# v1.net
KiCad netlist of a schematic drawn in EAGLE
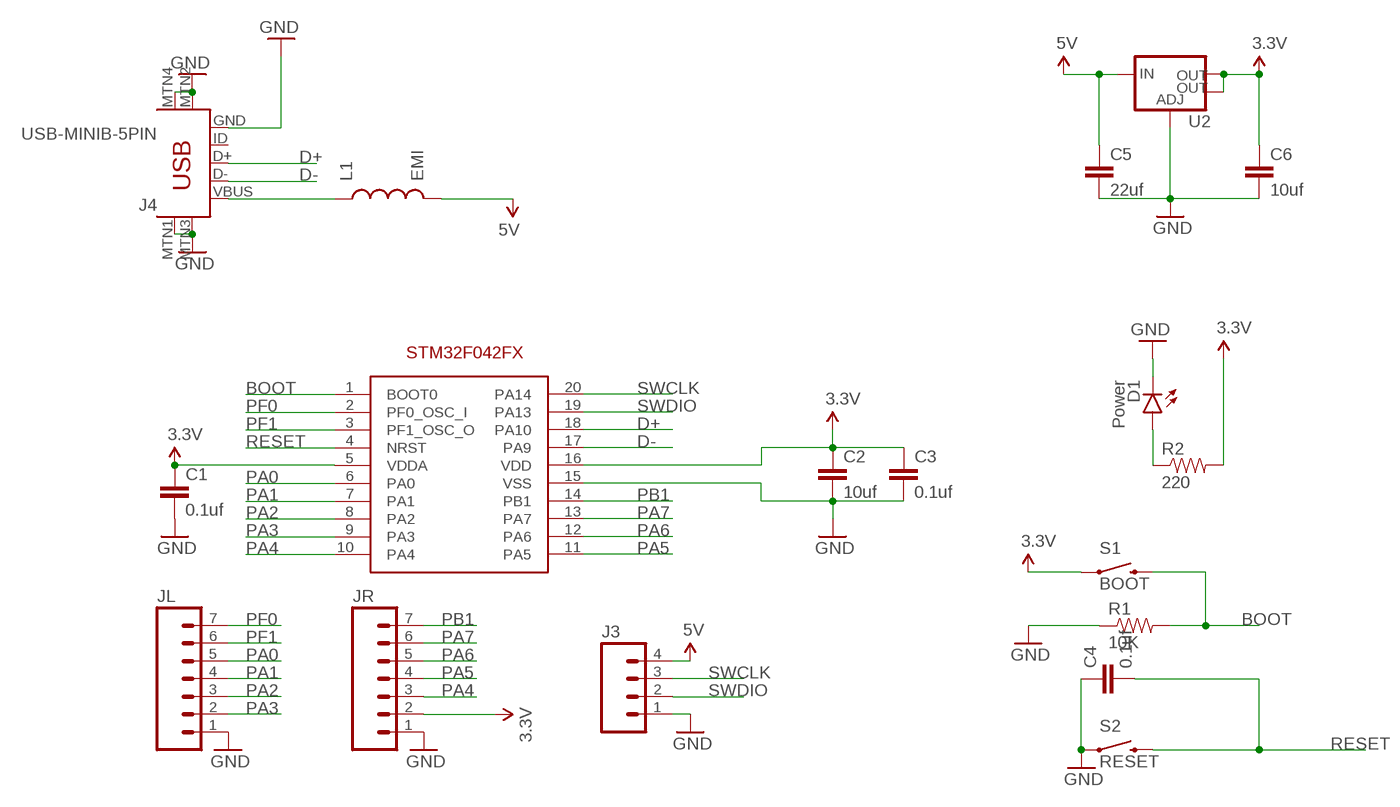
[diagram p0: schematic, sheet 1]

(export (version "E")
  (design (tool "Eeschema 10.0.6"))
  (components
    (comp (ref "C1")
      (value "0.1uf")
      (footprint "eagle-import:0805")
      (libsource (lib "eagle-import") (part "CAP0805"))
    )
    (comp (ref "C2")
      (value "10uf")
      (footprint "eagle-import:0805")
      (libsource (lib "eagle-import") (part "CAP0805"))
    )
    (comp (ref "C3")
      (value "0.1uf")
      (footprint "eagle-import:0805")
      (libsource (lib "eagle-import") (part "CAP0805"))
    )
    (comp (ref "C4")
      (value "0.1uf")
      (footprint "eagle-import:0805")
      (libsource (lib "eagle-import") (part "CAP0805"))
    )
    (comp (ref "C5")
      (value "22uf")
      (footprint "eagle-import:0805")
      (libsource (lib "eagle-import") (part "CAP0805"))
    )
    (comp (ref "C6")
      (value "10uf")
      (footprint "eagle-import:0805")
      (libsource (lib "eagle-import") (part "CAP0805"))
    )
    (comp (ref "D1")
      (value "Power")
      (footprint "eagle-import:LED-1206")
      (libsource (lib "eagle-import") (part "LED1206"))
    )
    (comp (ref "J3")
      (value "M04NO_SILK_ALL_ROUND")
      (footprint "eagle-import:1X04_NO_SILK_ALL_ROUND")
      (libsource (lib "eagle-import") (part "M04NO_SILK_ALL_ROUND"))
    )
    (comp (ref "J4")
      (value "USB-MINIB-5PIN")
      (footprint "eagle-import:USB-MINIB")
      (libsource (lib "eagle-import") (part "USB-MINIB-5PIN"))
    )
    (comp (ref "JL")
      (value "M07NO_SILK")
      (footprint "eagle-import:1X07_NO_SILK")
      (libsource (lib "eagle-import") (part "M07NO_SILK"))
    )
    (comp (ref "JR")
      (value "M07NO_SILK")
      (footprint "eagle-import:1X07_NO_SILK")
      (libsource (lib "eagle-import") (part "M07NO_SILK"))
    )
    (comp (ref "L1")
      (value "EMI")
      (footprint "eagle-import:0805")
      (libsource (lib "eagle-import") (part "INDUCTOR0805"))
    )
    (comp (ref "R1")
      (value "10K")
      (footprint "eagle-import:0805")
      (libsource (lib "eagle-import") (part "RESISTOR0805-RES"))
    )
    (comp (ref "R2")
      (value "220")
      (footprint "eagle-import:0805")
      (libsource (lib "eagle-import") (part "RESISTOR0805-RES"))
    )
    (comp (ref "S1")
      (value "BOOT")
      (footprint "eagle-import:TACTILE-SWITCH-1101NE")
      (libsource (lib "eagle-import") (part "SWITCH-MOMENTARY-2SMD-1101NE"))
    )
    (comp (ref "S2")
      (value "RESET")
      (footprint "eagle-import:TACTILE-SWITCH-1101NE")
      (libsource (lib "eagle-import") (part "SWITCH-MOMENTARY-2SMD-1101NE"))
    )
    (comp (ref "U1")
      (value "STM32F042FX")
      (footprint "eagle-import:TSSOP20")
      (libsource (lib "eagle-import") (part "STM32F042FX"))
    )
    (comp (ref "U2")
      (value "V_REG_LM1117SOT223")
      (footprint "eagle-import:SOT223")
      (libsource (lib "eagle-import") (part "V_REG_LM1117SOT223"))
    )
  )
  (nets
    (net (code "1") (name "/BOOT") (class "Default")
      (node (ref "R1") (pin "2") (pinfunction "2_2") (pintype "passive"))
      (node (ref "S1") (pin "2") (pinfunction "2_2") (pintype "passive"))
      (node (ref "U1") (pin "1") (pinfunction "BOOT0_1") (pintype "bidirectional"))
    )
    (net (code "2") (name "/D+") (class "Default")
      (node (ref "J4") (pin "D+") (pinfunction "D+_D+") (pintype "bidirectional"))
      (node (ref "U1") (pin "18") (pinfunction "PA10_18") (pintype "bidirectional"))
    )
    (net (code "3") (name "/D-") (class "Default")
      (node (ref "J4") (pin "D-") (pinfunction "D-_D-") (pintype "bidirectional"))
      (node (ref "U1") (pin "17") (pinfunction "PA9_17") (pintype "bidirectional"))
    )
    (net (code "4") (name "/PA0") (class "Default")
      (node (ref "JL") (pin "5") (pinfunction "5_5") (pintype "passive"))
      (node (ref "U1") (pin "6") (pinfunction "PA0_6") (pintype "bidirectional"))
    )
    (net (code "5") (name "/PA1") (class "Default")
      (node (ref "JL") (pin "4") (pinfunction "4_4") (pintype "passive"))
      (node (ref "U1") (pin "7") (pinfunction "PA1_7") (pintype "bidirectional"))
    )
    (net (code "6") (name "/PA2") (class "Default")
      (node (ref "JL") (pin "3") (pinfunction "3_3") (pintype "passive"))
      (node (ref "U1") (pin "8") (pinfunction "PA2_8") (pintype "bidirectional"))
    )
    (net (code "7") (name "/PA3") (class "Default")
      (node (ref "JL") (pin "2") (pinfunction "2_2") (pintype "passive"))
      (node (ref "U1") (pin "9") (pinfunction "PA3_9") (pintype "bidirectional"))
    )
    (net (code "8") (name "/PA4") (class "Default")
      (node (ref "JR") (pin "3") (pinfunction "3_3") (pintype "passive"))
      (node (ref "U1") (pin "10") (pinfunction "PA4_10") (pintype "bidirectional"))
    )
    (net (code "9") (name "/PA5") (class "Default")
      (node (ref "JR") (pin "4") (pinfunction "4_4") (pintype "passive"))
      (node (ref "U1") (pin "11") (pinfunction "PA5_11") (pintype "bidirectional"))
    )
    (net (code "10") (name "/PA6") (class "Default")
      (node (ref "JR") (pin "5") (pinfunction "5_5") (pintype "passive"))
      (node (ref "U1") (pin "12") (pinfunction "PA6_12") (pintype "bidirectional"))
    )
    (net (code "11") (name "/PA7") (class "Default")
      (node (ref "JR") (pin "6") (pinfunction "6_6") (pintype "passive"))
      (node (ref "U1") (pin "13") (pinfunction "PA7_13") (pintype "bidirectional"))
    )
    (net (code "12") (name "/PB1") (class "Default")
      (node (ref "JR") (pin "7") (pinfunction "7_7") (pintype "passive"))
      (node (ref "U1") (pin "14") (pinfunction "PB1_14") (pintype "bidirectional"))
    )
    (net (code "13") (name "/PF0") (class "Default")
      (node (ref "JL") (pin "7") (pinfunction "7_7") (pintype "passive"))
      (node (ref "U1") (pin "2") (pinfunction "PF0_OSC_I_2") (pintype "bidirectional"))
    )
    (net (code "14") (name "/PF1") (class "Default")
      (node (ref "JL") (pin "6") (pinfunction "6_6") (pintype "passive"))
      (node (ref "U1") (pin "3") (pinfunction "PF1_OSC_O_3") (pintype "bidirectional"))
    )
    (net (code "15") (name "/RESET") (class "Default")
      (node (ref "C4") (pin "2") (pinfunction "2_2") (pintype "passive"))
      (node (ref "S2") (pin "2") (pinfunction "2_2") (pintype "passive"))
      (node (ref "U1") (pin "4") (pinfunction "NRST_4") (pintype "input"))
    )
    (net (code "16") (name "/SWCLK") (class "Default")
      (node (ref "J3") (pin "3") (pinfunction "3_3") (pintype "passive"))
      (node (ref "U1") (pin "20") (pinfunction "PA14_20") (pintype "bidirectional"))
    )
    (net (code "17") (name "/SWDIO") (class "Default")
      (node (ref "J3") (pin "2") (pinfunction "2_2") (pintype "passive"))
      (node (ref "U1") (pin "19") (pinfunction "PA13_19") (pintype "bidirectional"))
    )
    (net (code "18") (name "3.3V") (class "Default")
      (node (ref "C1") (pin "1") (pinfunction "1_1") (pintype "passive"))
      (node (ref "C2") (pin "1") (pinfunction "1_1") (pintype "passive"))
      (node (ref "C3") (pin "1") (pinfunction "1_1") (pintype "passive"))
      (node (ref "C6") (pin "1") (pinfunction "1_1") (pintype "passive"))
      (node (ref "JR") (pin "2") (pinfunction "2_2") (pintype "passive"))
      (node (ref "R2") (pin "2") (pinfunction "2_2") (pintype "passive"))
      (node (ref "S1") (pin "1") (pinfunction "1_1") (pintype "passive"))
      (node (ref "U1") (pin "16") (pinfunction "VDD_16") (pintype "power_in"))
      (node (ref "U1") (pin "5") (pinfunction "VDDA_5") (pintype "power_in"))
      (node (ref "U2") (pin "2") (pinfunction "OUT_2") (pintype "output"))
      (node (ref "U2") (pin "4") (pinfunction "OUT_4") (pintype "output"))
    )
    (net (code "19") (name "5V") (class "Default")
      (node (ref "C5") (pin "1") (pinfunction "1_1") (pintype "passive"))
      (node (ref "J3") (pin "4") (pinfunction "4_4") (pintype "passive"))
      (node (ref "L1") (pin "2") (pinfunction "2_2") (pintype "passive"))
      (node (ref "U2") (pin "3") (pinfunction "IN_3") (pintype "input"))
    )
    (net (code "20") (name "GND") (class "Default")
      (node (ref "C1") (pin "2") (pinfunction "2_2") (pintype "passive"))
      (node (ref "C2") (pin "2") (pinfunction "2_2") (pintype "passive"))
      (node (ref "C3") (pin "2") (pinfunction "2_2") (pintype "passive"))
      (node (ref "C4") (pin "1") (pinfunction "1_1") (pintype "passive"))
      (node (ref "C5") (pin "2") (pinfunction "2_2") (pintype "passive"))
      (node (ref "C6") (pin "2") (pinfunction "2_2") (pintype "passive"))
      (node (ref "D1") (pin "C") (pinfunction "C_C") (pintype "passive"))
      (node (ref "J3") (pin "1") (pinfunction "1_1") (pintype "passive"))
      (node (ref "J4") (pin "GND") (pinfunction "GND_GND") (pintype "bidirectional"))
      (node (ref "J4") (pin "MTN1") (pinfunction "MTN2_MTN1") (pintype "bidirectional"))
      (node (ref "J4") (pin "MTN2") (pinfunction "MTN3_MTN2") (pintype "bidirectional"))
      (node (ref "J4") (pin "MTN3") (pinfunction "MTN1_MTN3") (pintype "bidirectional"))
      (node (ref "J4") (pin "MTN4") (pinfunction "MTN4_MTN4") (pintype "bidirectional"))
      (node (ref "JL") (pin "1") (pinfunction "1_1") (pintype "passive"))
      (node (ref "JR") (pin "1") (pinfunction "1_1") (pintype "passive"))
      (node (ref "R1") (pin "1") (pinfunction "1_1") (pintype "passive"))
      (node (ref "S2") (pin "1") (pinfunction "1_1") (pintype "passive"))
      (node (ref "U1") (pin "15") (pinfunction "VSS_15") (pintype "power_in"))
      (node (ref "U2") (pin "1") (pinfunction "ADJ_1") (pintype "input"))
    )
    (net (code "21") (name "Net-(D1-PadA)") (class "Default")
      (node (ref "D1") (pin "A") (pinfunction "A_A") (pintype "passive"))
      (node (ref "R2") (pin "1") (pinfunction "1_1") (pintype "passive"))
    )
    (net (code "22") (name "Net-(J4-PadVBUS)") (class "Default")
      (node (ref "J4") (pin "VBUS") (pinfunction "VBUS_VBUS") (pintype "bidirectional"))
      (node (ref "L1") (pin "1") (pinfunction "1_1") (pintype "passive"))
    )
    (net (code "23") (name "unconnected-(J4-PadID)") (class "Default")
      (node (ref "J4") (pin "ID") (pinfunction "ID_ID") (pintype "bidirectional"))
    )
  )
)
